# shiva.net
KiCad netlist of a schematic drawn in EAGLE
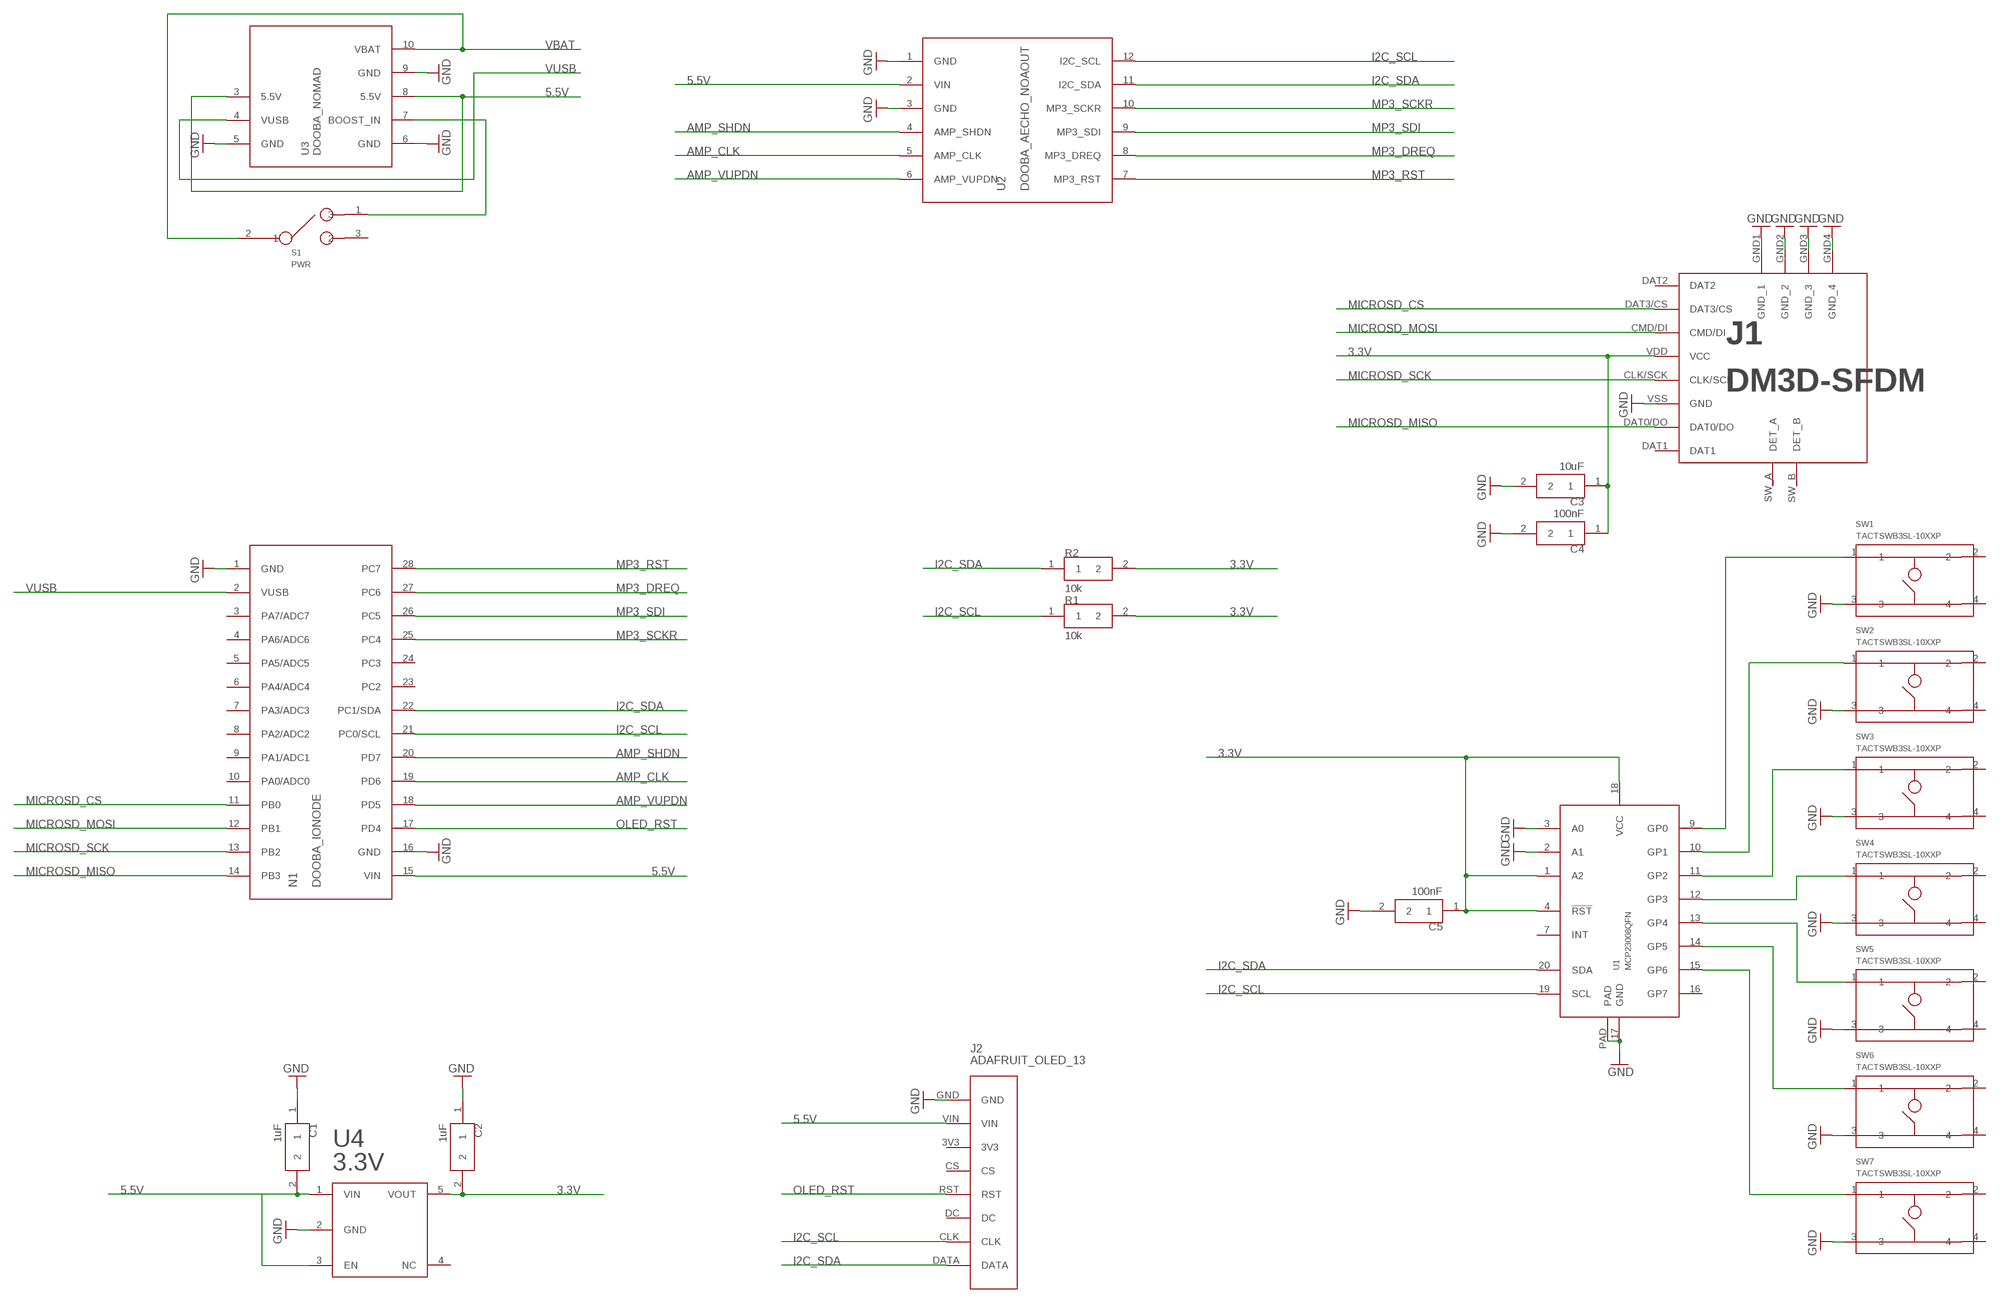
[diagram p0: schematic, sheet 1]

(export (version "E")
  (design (tool "Eeschema 10.0.6"))
  (components
    (comp (ref "C1")
      (value "1uF")
      (footprint "eagle-import:0805")
      (libsource (lib "eagle-import") (part "CAP0805"))
    )
    (comp (ref "C2")
      (value "1uF")
      (footprint "eagle-import:0805")
      (libsource (lib "eagle-import") (part "CAP0805"))
    )
    (comp (ref "C3")
      (value "10uF")
      (footprint "eagle-import:0805")
      (libsource (lib "eagle-import") (part "CAP0805"))
    )
    (comp (ref "C4")
      (value "100nF")
      (footprint "eagle-import:0805")
      (libsource (lib "eagle-import") (part "CAP0805"))
    )
    (comp (ref "C5")
      (value "100nF")
      (footprint "eagle-import:0805")
      (libsource (lib "eagle-import") (part "CAP0805"))
    )
    (comp (ref "J1")
      (value "DM3D-SFDM")
      (footprint "eagle-import:DM3D-SF")
      (libsource (lib "eagle-import") (part "DM3D-SFDM"))
    )
    (comp (ref "J2")
      (value "ADAFRUIT_OLED_13")
      (footprint "eagle-import:ADAFRUIT_OLED_13")
      (libsource (lib "eagle-import") (part "ADAFRUIT_OLED_13"))
    )
    (comp (ref "N1")
      (value "DOOBA_IONODE")
      (footprint "eagle-import:DOOBA_IONODE")
      (libsource (lib "eagle-import") (part "DOOBA_IONODE"))
    )
    (comp (ref "R1")
      (value "10k")
      (footprint "eagle-import:0805")
      (libsource (lib "eagle-import") (part "RES0805"))
    )
    (comp (ref "R2")
      (value "10k")
      (footprint "eagle-import:0805")
      (libsource (lib "eagle-import") (part "RES0805"))
    )
    (comp (ref "S1")
      (value "PWR")
      (footprint "eagle-import:JS102011")
      (libsource (lib "eagle-import") (part "SWITCH_SPDT"))
    )
    (comp (ref "SW1")
      (value "TACTSWB3SL-10XXP")
      (footprint "eagle-import:B3SL-10XXP")
      (libsource (lib "eagle-import") (part "TACTSWB3SL-10XXP"))
    )
    (comp (ref "SW2")
      (value "TACTSWB3SL-10XXP")
      (footprint "eagle-import:B3SL-10XXP")
      (libsource (lib "eagle-import") (part "TACTSWB3SL-10XXP"))
    )
    (comp (ref "SW3")
      (value "TACTSWB3SL-10XXP")
      (footprint "eagle-import:B3SL-10XXP")
      (libsource (lib "eagle-import") (part "TACTSWB3SL-10XXP"))
    )
    (comp (ref "SW4")
      (value "TACTSWB3SL-10XXP")
      (footprint "eagle-import:B3SL-10XXP")
      (libsource (lib "eagle-import") (part "TACTSWB3SL-10XXP"))
    )
    (comp (ref "SW5")
      (value "TACTSWB3SL-10XXP")
      (footprint "eagle-import:B3SL-10XXP")
      (libsource (lib "eagle-import") (part "TACTSWB3SL-10XXP"))
    )
    (comp (ref "SW6")
      (value "TACTSWB3SL-10XXP")
      (footprint "eagle-import:B3SL-10XXP")
      (libsource (lib "eagle-import") (part "TACTSWB3SL-10XXP"))
    )
    (comp (ref "SW7")
      (value "TACTSWB3SL-10XXP")
      (footprint "eagle-import:B3SL-10XXP")
      (libsource (lib "eagle-import") (part "TACTSWB3SL-10XXP"))
    )
    (comp (ref "U1")
      (value "MCP23008QFN")
      (footprint "eagle-import:20-VQFN")
      (libsource (lib "eagle-import") (part "MCP23008QFN"))
    )
    (comp (ref "U2")
      (value "DOOBA_AECHO_NOAOUT")
      (footprint "eagle-import:DOOBA_AECHO_NOAOUT")
      (libsource (lib "eagle-import") (part "DOOBA_AECHO_NOAOUT"))
    )
    (comp (ref "U3")
      (value "DOOBA_NOMAD")
      (footprint "eagle-import:DOOBA_NOMAD")
      (libsource (lib "eagle-import") (part "DOOBA_NOMAD"))
    )
    (comp (ref "U4")
      (value "3.3V")
      (footprint "eagle-import:SOT23-5")
      (libsource (lib "eagle-import") (part "LP3985SOT23-5"))
    )
  )
  (nets
    (net (code "1") (name "/3.3V") (class "Default")
      (node (ref "C2") (pin "2") (pinfunction "2_2") (pintype "bidirectional"))
      (node (ref "C3") (pin "1") (pinfunction "1_1") (pintype "bidirectional"))
      (node (ref "C4") (pin "1") (pinfunction "1_1") (pintype "bidirectional"))
      (node (ref "C5") (pin "1") (pinfunction "1_1") (pintype "bidirectional"))
      (node (ref "J1") (pin "VDD") (pinfunction "VCC_VDD") (pintype "bidirectional"))
      (node (ref "R1") (pin "2") (pinfunction "2_2") (pintype "bidirectional"))
      (node (ref "R2") (pin "2") (pinfunction "2_2") (pintype "bidirectional"))
      (node (ref "U1") (pin "1") (pinfunction "A2_1") (pintype "bidirectional"))
      (node (ref "U1") (pin "18") (pinfunction "VCC_18") (pintype "bidirectional"))
      (node (ref "U1") (pin "4") (pinfunction "~{RST}_4") (pintype "bidirectional"))
      (node (ref "U4") (pin "5") (pinfunction "VOUT_5") (pintype "bidirectional"))
    )
    (net (code "2") (name "/5.5V") (class "Default")
      (node (ref "C1") (pin "2") (pinfunction "2_2") (pintype "bidirectional"))
      (node (ref "J2") (pin "VIN") (pinfunction "VIN_VIN") (pintype "bidirectional"))
      (node (ref "N1") (pin "15") (pinfunction "VIN_15") (pintype "bidirectional"))
      (node (ref "U2") (pin "2") (pinfunction "VIN_2") (pintype "bidirectional"))
      (node (ref "U3") (pin "3") (pinfunction "5.5V_3") (pintype "bidirectional"))
      (node (ref "U3") (pin "8") (pinfunction "5.5V_8") (pintype "bidirectional"))
      (node (ref "U4") (pin "1") (pinfunction "VIN_1") (pintype "bidirectional"))
      (node (ref "U4") (pin "3") (pinfunction "EN_3") (pintype "bidirectional"))
    )
    (net (code "3") (name "/AMP_CLK") (class "Default")
      (node (ref "N1") (pin "19") (pinfunction "PD6_19") (pintype "bidirectional"))
      (node (ref "U2") (pin "5") (pinfunction "AMP_CLK_5") (pintype "bidirectional"))
    )
    (net (code "4") (name "/AMP_SHDN") (class "Default")
      (node (ref "N1") (pin "20") (pinfunction "PD7_20") (pintype "bidirectional"))
      (node (ref "U2") (pin "4") (pinfunction "AMP_SHDN_4") (pintype "bidirectional"))
    )
    (net (code "5") (name "/AMP_VUPDN") (class "Default")
      (node (ref "N1") (pin "18") (pinfunction "PD5_18") (pintype "bidirectional"))
      (node (ref "U2") (pin "6") (pinfunction "AMP_VUPDN_6") (pintype "bidirectional"))
    )
    (net (code "6") (name "/I2C_SCL") (class "Default")
      (node (ref "J2") (pin "CLK") (pinfunction "CLK_CLK") (pintype "bidirectional"))
      (node (ref "N1") (pin "21") (pinfunction "PC0/SCL_21") (pintype "bidirectional"))
      (node (ref "R1") (pin "1") (pinfunction "1_1") (pintype "bidirectional"))
      (node (ref "U1") (pin "19") (pinfunction "SCL_19") (pintype "bidirectional"))
      (node (ref "U2") (pin "12") (pinfunction "I2C_SCL_12") (pintype "bidirectional"))
    )
    (net (code "7") (name "/I2C_SDA") (class "Default")
      (node (ref "J2") (pin "DATA") (pinfunction "DATA_DATA") (pintype "bidirectional"))
      (node (ref "N1") (pin "22") (pinfunction "PC1/SDA_22") (pintype "bidirectional"))
      (node (ref "R2") (pin "1") (pinfunction "1_1") (pintype "bidirectional"))
      (node (ref "U1") (pin "20") (pinfunction "SDA_20") (pintype "bidirectional"))
      (node (ref "U2") (pin "11") (pinfunction "I2C_SDA_11") (pintype "bidirectional"))
    )
    (net (code "8") (name "/MICROSD_CS") (class "Default")
      (node (ref "J1") (pin "DAT3/CS") (pinfunction "DAT3/CS_DAT3/CS") (pintype "bidirectional"))
      (node (ref "N1") (pin "11") (pinfunction "PB0_11") (pintype "bidirectional"))
    )
    (net (code "9") (name "/MICROSD_MISO") (class "Default")
      (node (ref "J1") (pin "DAT0/DO") (pinfunction "DAT0/DO_DAT0/DO") (pintype "bidirectional"))
      (node (ref "N1") (pin "14") (pinfunction "PB3_14") (pintype "bidirectional"))
    )
    (net (code "10") (name "/MICROSD_MOSI") (class "Default")
      (node (ref "J1") (pin "CMD/DI") (pinfunction "CMD/DI_CMD/DI") (pintype "bidirectional"))
      (node (ref "N1") (pin "12") (pinfunction "PB1_12") (pintype "bidirectional"))
    )
    (net (code "11") (name "/MICROSD_SCK") (class "Default")
      (node (ref "J1") (pin "CLK/SCK") (pinfunction "CLK/SCK_CLK/SCK") (pintype "bidirectional"))
      (node (ref "N1") (pin "13") (pinfunction "PB2_13") (pintype "bidirectional"))
    )
    (net (code "12") (name "/MP3_DREQ") (class "Default")
      (node (ref "N1") (pin "27") (pinfunction "PC6_27") (pintype "bidirectional"))
      (node (ref "U2") (pin "8") (pinfunction "MP3_DREQ_8") (pintype "bidirectional"))
    )
    (net (code "13") (name "/MP3_RST") (class "Default")
      (node (ref "N1") (pin "28") (pinfunction "PC7_28") (pintype "bidirectional"))
      (node (ref "U2") (pin "7") (pinfunction "MP3_RST_7") (pintype "bidirectional"))
    )
    (net (code "14") (name "/MP3_SCKR") (class "Default")
      (node (ref "N1") (pin "25") (pinfunction "PC4_25") (pintype "bidirectional"))
      (node (ref "U2") (pin "10") (pinfunction "MP3_SCKR_10") (pintype "bidirectional"))
    )
    (net (code "15") (name "/MP3_SDI") (class "Default")
      (node (ref "N1") (pin "26") (pinfunction "PC5_26") (pintype "bidirectional"))
      (node (ref "U2") (pin "9") (pinfunction "MP3_SDI_9") (pintype "bidirectional"))
    )
    (net (code "16") (name "/OLED_RST") (class "Default")
      (node (ref "J2") (pin "RST") (pinfunction "RST_RST") (pintype "bidirectional"))
      (node (ref "N1") (pin "17") (pinfunction "PD4_17") (pintype "bidirectional"))
    )
    (net (code "17") (name "/VBAT") (class "Default")
      (node (ref "S1") (pin "2") (pinfunction "1_2") (pintype "bidirectional"))
      (node (ref "U3") (pin "10") (pinfunction "VBAT_10") (pintype "bidirectional"))
    )
    (net (code "18") (name "/VUSB") (class "Default")
      (node (ref "N1") (pin "2") (pinfunction "VUSB_2") (pintype "bidirectional"))
      (node (ref "U3") (pin "4") (pinfunction "VUSB_4") (pintype "bidirectional"))
    )
    (net (code "19") (name "GND") (class "Default")
      (node (ref "C1") (pin "1") (pinfunction "1_1") (pintype "bidirectional"))
      (node (ref "C2") (pin "1") (pinfunction "1_1") (pintype "bidirectional"))
      (node (ref "C3") (pin "2") (pinfunction "2_2") (pintype "bidirectional"))
      (node (ref "C4") (pin "2") (pinfunction "2_2") (pintype "bidirectional"))
      (node (ref "C5") (pin "2") (pinfunction "2_2") (pintype "bidirectional"))
      (node (ref "J1") (pin "GND1") (pinfunction "GND_1_GND1") (pintype "bidirectional"))
      (node (ref "J1") (pin "GND2") (pinfunction "GND_2_GND2") (pintype "bidirectional"))
      (node (ref "J1") (pin "GND3") (pinfunction "GND_3_GND3") (pintype "bidirectional"))
      (node (ref "J1") (pin "GND4") (pinfunction "GND_4_GND4") (pintype "bidirectional"))
      (node (ref "J1") (pin "VSS") (pinfunction "GND_VSS") (pintype "bidirectional"))
      (node (ref "J2") (pin "GND") (pinfunction "GND_GND") (pintype "bidirectional"))
      (node (ref "N1") (pin "1") (pinfunction "GND_1") (pintype "bidirectional"))
      (node (ref "N1") (pin "16") (pinfunction "GND_16") (pintype "bidirectional"))
      (node (ref "SW1") (pin "3") (pinfunction "3_3") (pintype "bidirectional"))
      (node (ref "SW2") (pin "3") (pinfunction "3_3") (pintype "bidirectional"))
      (node (ref "SW3") (pin "3") (pinfunction "3_3") (pintype "bidirectional"))
      (node (ref "SW4") (pin "3") (pinfunction "3_3") (pintype "bidirectional"))
      (node (ref "SW5") (pin "3") (pinfunction "3_3") (pintype "bidirectional"))
      (node (ref "SW6") (pin "3") (pinfunction "3_3") (pintype "bidirectional"))
      (node (ref "SW7") (pin "3") (pinfunction "3_3") (pintype "bidirectional"))
      (node (ref "U1") (pin "17") (pinfunction "GND_17") (pintype "bidirectional"))
      (node (ref "U1") (pin "2") (pinfunction "A1_2") (pintype "bidirectional"))
      (node (ref "U1") (pin "3") (pinfunction "A0_3") (pintype "bidirectional"))
      (node (ref "U1") (pin "PAD") (pinfunction "PAD_PAD") (pintype "bidirectional"))
      (node (ref "U2") (pin "1") (pinfunction "GND_1") (pintype "bidirectional"))
      (node (ref "U2") (pin "3") (pinfunction "GND_3") (pintype "bidirectional"))
      (node (ref "U3") (pin "5") (pinfunction "GND_5") (pintype "bidirectional"))
      (node (ref "U3") (pin "6") (pinfunction "GND_6") (pintype "bidirectional"))
      (node (ref "U3") (pin "9") (pinfunction "GND_9") (pintype "bidirectional"))
      (node (ref "U4") (pin "2") (pinfunction "GND_2") (pintype "bidirectional"))
    )
    (net (code "20") (name "Net-(S1-3)") (class "Default")
      (node (ref "S1") (pin "1") (pinfunction "3_1") (pintype "bidirectional"))
      (node (ref "U3") (pin "7") (pinfunction "BOOST_IN_7") (pintype "bidirectional"))
    )
    (net (code "21") (name "Net-(U1-GP0)") (class "Default")
      (node (ref "SW1") (pin "1") (pinfunction "1_1") (pintype "bidirectional"))
      (node (ref "U1") (pin "9") (pinfunction "GP0_9") (pintype "bidirectional"))
    )
    (net (code "22") (name "Net-(U1-GP1)") (class "Default")
      (node (ref "SW2") (pin "1") (pinfunction "1_1") (pintype "bidirectional"))
      (node (ref "U1") (pin "10") (pinfunction "GP1_10") (pintype "bidirectional"))
    )
    (net (code "23") (name "Net-(U1-GP2)") (class "Default")
      (node (ref "SW3") (pin "1") (pinfunction "1_1") (pintype "bidirectional"))
      (node (ref "U1") (pin "11") (pinfunction "GP2_11") (pintype "bidirectional"))
    )
    (net (code "24") (name "Net-(U1-GP3)") (class "Default")
      (node (ref "SW4") (pin "1") (pinfunction "1_1") (pintype "bidirectional"))
      (node (ref "U1") (pin "12") (pinfunction "GP3_12") (pintype "bidirectional"))
    )
    (net (code "25") (name "Net-(U1-GP4)") (class "Default")
      (node (ref "SW5") (pin "1") (pinfunction "1_1") (pintype "bidirectional"))
      (node (ref "U1") (pin "13") (pinfunction "GP4_13") (pintype "bidirectional"))
    )
    (net (code "26") (name "Net-(U1-GP5)") (class "Default")
      (node (ref "SW6") (pin "1") (pinfunction "1_1") (pintype "bidirectional"))
      (node (ref "U1") (pin "14") (pinfunction "GP5_14") (pintype "bidirectional"))
    )
    (net (code "27") (name "Net-(U1-GP6)") (class "Default")
      (node (ref "SW7") (pin "1") (pinfunction "1_1") (pintype "bidirectional"))
      (node (ref "U1") (pin "15") (pinfunction "GP6_15") (pintype "bidirectional"))
    )
    (net (code "28") (name "unconnected-(J1-DET_A-PadSW_A)") (class "Default")
      (node (ref "J1") (pin "SW_A") (pinfunction "DET_A_SW_A") (pintype "bidirectional"))
    )
    (net (code "29") (name "unconnected-(J1-DET_B-PadSW_B)") (class "Default")
      (node (ref "J1") (pin "SW_B") (pinfunction "DET_B_SW_B") (pintype "bidirectional"))
    )
    (net (code "30") (name "unconnected-(J1-PadDAT1)") (class "Default")
      (node (ref "J1") (pin "DAT1") (pinfunction "DAT1_DAT1") (pintype "bidirectional"))
    )
    (net (code "31") (name "unconnected-(J1-PadDAT2)") (class "Default")
      (node (ref "J1") (pin "DAT2") (pinfunction "DAT2_DAT2") (pintype "bidirectional"))
    )
    (net (code "32") (name "unconnected-(J2-Pad3V3)") (class "Default")
      (node (ref "J2") (pin "3V3") (pinfunction "3V3_3V3") (pintype "bidirectional"))
    )
    (net (code "33") (name "unconnected-(J2-PadCS)") (class "Default")
      (node (ref "J2") (pin "CS") (pinfunction "CS_CS") (pintype "bidirectional"))
    )
    (net (code "34") (name "unconnected-(J2-PadDC)") (class "Default")
      (node (ref "J2") (pin "DC") (pinfunction "DC_DC") (pintype "bidirectional"))
    )
    (net (code "35") (name "unconnected-(N1-PA0{slash}ADC0-Pad10)") (class "Default")
      (node (ref "N1") (pin "10") (pinfunction "PA0/ADC0_10") (pintype "bidirectional"))
    )
    (net (code "36") (name "unconnected-(N1-PA1{slash}ADC1-Pad9)") (class "Default")
      (node (ref "N1") (pin "9") (pinfunction "PA1/ADC1_9") (pintype "bidirectional"))
    )
    (net (code "37") (name "unconnected-(N1-PA2{slash}ADC2-Pad8)") (class "Default")
      (node (ref "N1") (pin "8") (pinfunction "PA2/ADC2_8") (pintype "bidirectional"))
    )
    (net (code "38") (name "unconnected-(N1-PA3{slash}ADC3-Pad7)") (class "Default")
      (node (ref "N1") (pin "7") (pinfunction "PA3/ADC3_7") (pintype "bidirectional"))
    )
    (net (code "39") (name "unconnected-(N1-PA4{slash}ADC4-Pad6)") (class "Default")
      (node (ref "N1") (pin "6") (pinfunction "PA4/ADC4_6") (pintype "bidirectional"))
    )
    (net (code "40") (name "unconnected-(N1-PA5{slash}ADC5-Pad5)") (class "Default")
      (node (ref "N1") (pin "5") (pinfunction "PA5/ADC5_5") (pintype "bidirectional"))
    )
    (net (code "41") (name "unconnected-(N1-PA6{slash}ADC6-Pad4)") (class "Default")
      (node (ref "N1") (pin "4") (pinfunction "PA6/ADC6_4") (pintype "bidirectional"))
    )
    (net (code "42") (name "unconnected-(N1-PA7{slash}ADC7-Pad3)") (class "Default")
      (node (ref "N1") (pin "3") (pinfunction "PA7/ADC7_3") (pintype "bidirectional"))
    )
    (net (code "43") (name "unconnected-(N1-PC2-Pad23)") (class "Default")
      (node (ref "N1") (pin "23") (pinfunction "PC2_23") (pintype "bidirectional"))
    )
    (net (code "44") (name "unconnected-(N1-PC3-Pad24)") (class "Default")
      (node (ref "N1") (pin "24") (pinfunction "PC3_24") (pintype "bidirectional"))
    )
    (net (code "45") (name "unconnected-(S1-2-Pad3)") (class "Default")
      (node (ref "S1") (pin "3") (pinfunction "2_3") (pintype "bidirectional"))
    )
    (net (code "46") (name "unconnected-(SW1-Pad2)") (class "Default")
      (node (ref "SW1") (pin "2") (pinfunction "2_2") (pintype "bidirectional"))
    )
    (net (code "47") (name "unconnected-(SW1-Pad4)") (class "Default")
      (node (ref "SW1") (pin "4") (pinfunction "4_4") (pintype "bidirectional"))
    )
    (net (code "48") (name "unconnected-(SW2-Pad2)") (class "Default")
      (node (ref "SW2") (pin "2") (pinfunction "2_2") (pintype "bidirectional"))
    )
    (net (code "49") (name "unconnected-(SW2-Pad4)") (class "Default")
      (node (ref "SW2") (pin "4") (pinfunction "4_4") (pintype "bidirectional"))
    )
    (net (code "50") (name "unconnected-(SW3-Pad2)") (class "Default")
      (node (ref "SW3") (pin "2") (pinfunction "2_2") (pintype "bidirectional"))
    )
    (net (code "51") (name "unconnected-(SW3-Pad4)") (class "Default")
      (node (ref "SW3") (pin "4") (pinfunction "4_4") (pintype "bidirectional"))
    )
    (net (code "52") (name "unconnected-(SW4-Pad2)") (class "Default")
      (node (ref "SW4") (pin "2") (pinfunction "2_2") (pintype "bidirectional"))
    )
    (net (code "53") (name "unconnected-(SW4-Pad4)") (class "Default")
      (node (ref "SW4") (pin "4") (pinfunction "4_4") (pintype "bidirectional"))
    )
    (net (code "54") (name "unconnected-(SW5-Pad2)") (class "Default")
      (node (ref "SW5") (pin "2") (pinfunction "2_2") (pintype "bidirectional"))
    )
    (net (code "55") (name "unconnected-(SW5-Pad4)") (class "Default")
      (node (ref "SW5") (pin "4") (pinfunction "4_4") (pintype "bidirectional"))
    )
    (net (code "56") (name "unconnected-(SW6-Pad2)") (class "Default")
      (node (ref "SW6") (pin "2") (pinfunction "2_2") (pintype "bidirectional"))
    )
    (net (code "57") (name "unconnected-(SW6-Pad4)") (class "Default")
      (node (ref "SW6") (pin "4") (pinfunction "4_4") (pintype "bidirectional"))
    )
    (net (code "58") (name "unconnected-(SW7-Pad2)") (class "Default")
      (node (ref "SW7") (pin "2") (pinfunction "2_2") (pintype "bidirectional"))
    )
    (net (code "59") (name "unconnected-(SW7-Pad4)") (class "Default")
      (node (ref "SW7") (pin "4") (pinfunction "4_4") (pintype "bidirectional"))
    )
    (net (code "60") (name "unconnected-(U1-GP7-Pad16)") (class "Default")
      (node (ref "U1") (pin "16") (pinfunction "GP7_16") (pintype "bidirectional"))
    )
    (net (code "61") (name "unconnected-(U1-INT-Pad7)") (class "Default")
      (node (ref "U1") (pin "7") (pinfunction "INT_7") (pintype "bidirectional"))
    )
    (net (code "62") (name "unconnected-(U4-NC-Pad4)") (class "Default")
      (node (ref "U4") (pin "4") (pinfunction "NC_4") (pintype "bidirectional"))
    )
  )
)
